# RGB-mic.net
KiCad netlist of a schematic drawn in Altium Designer
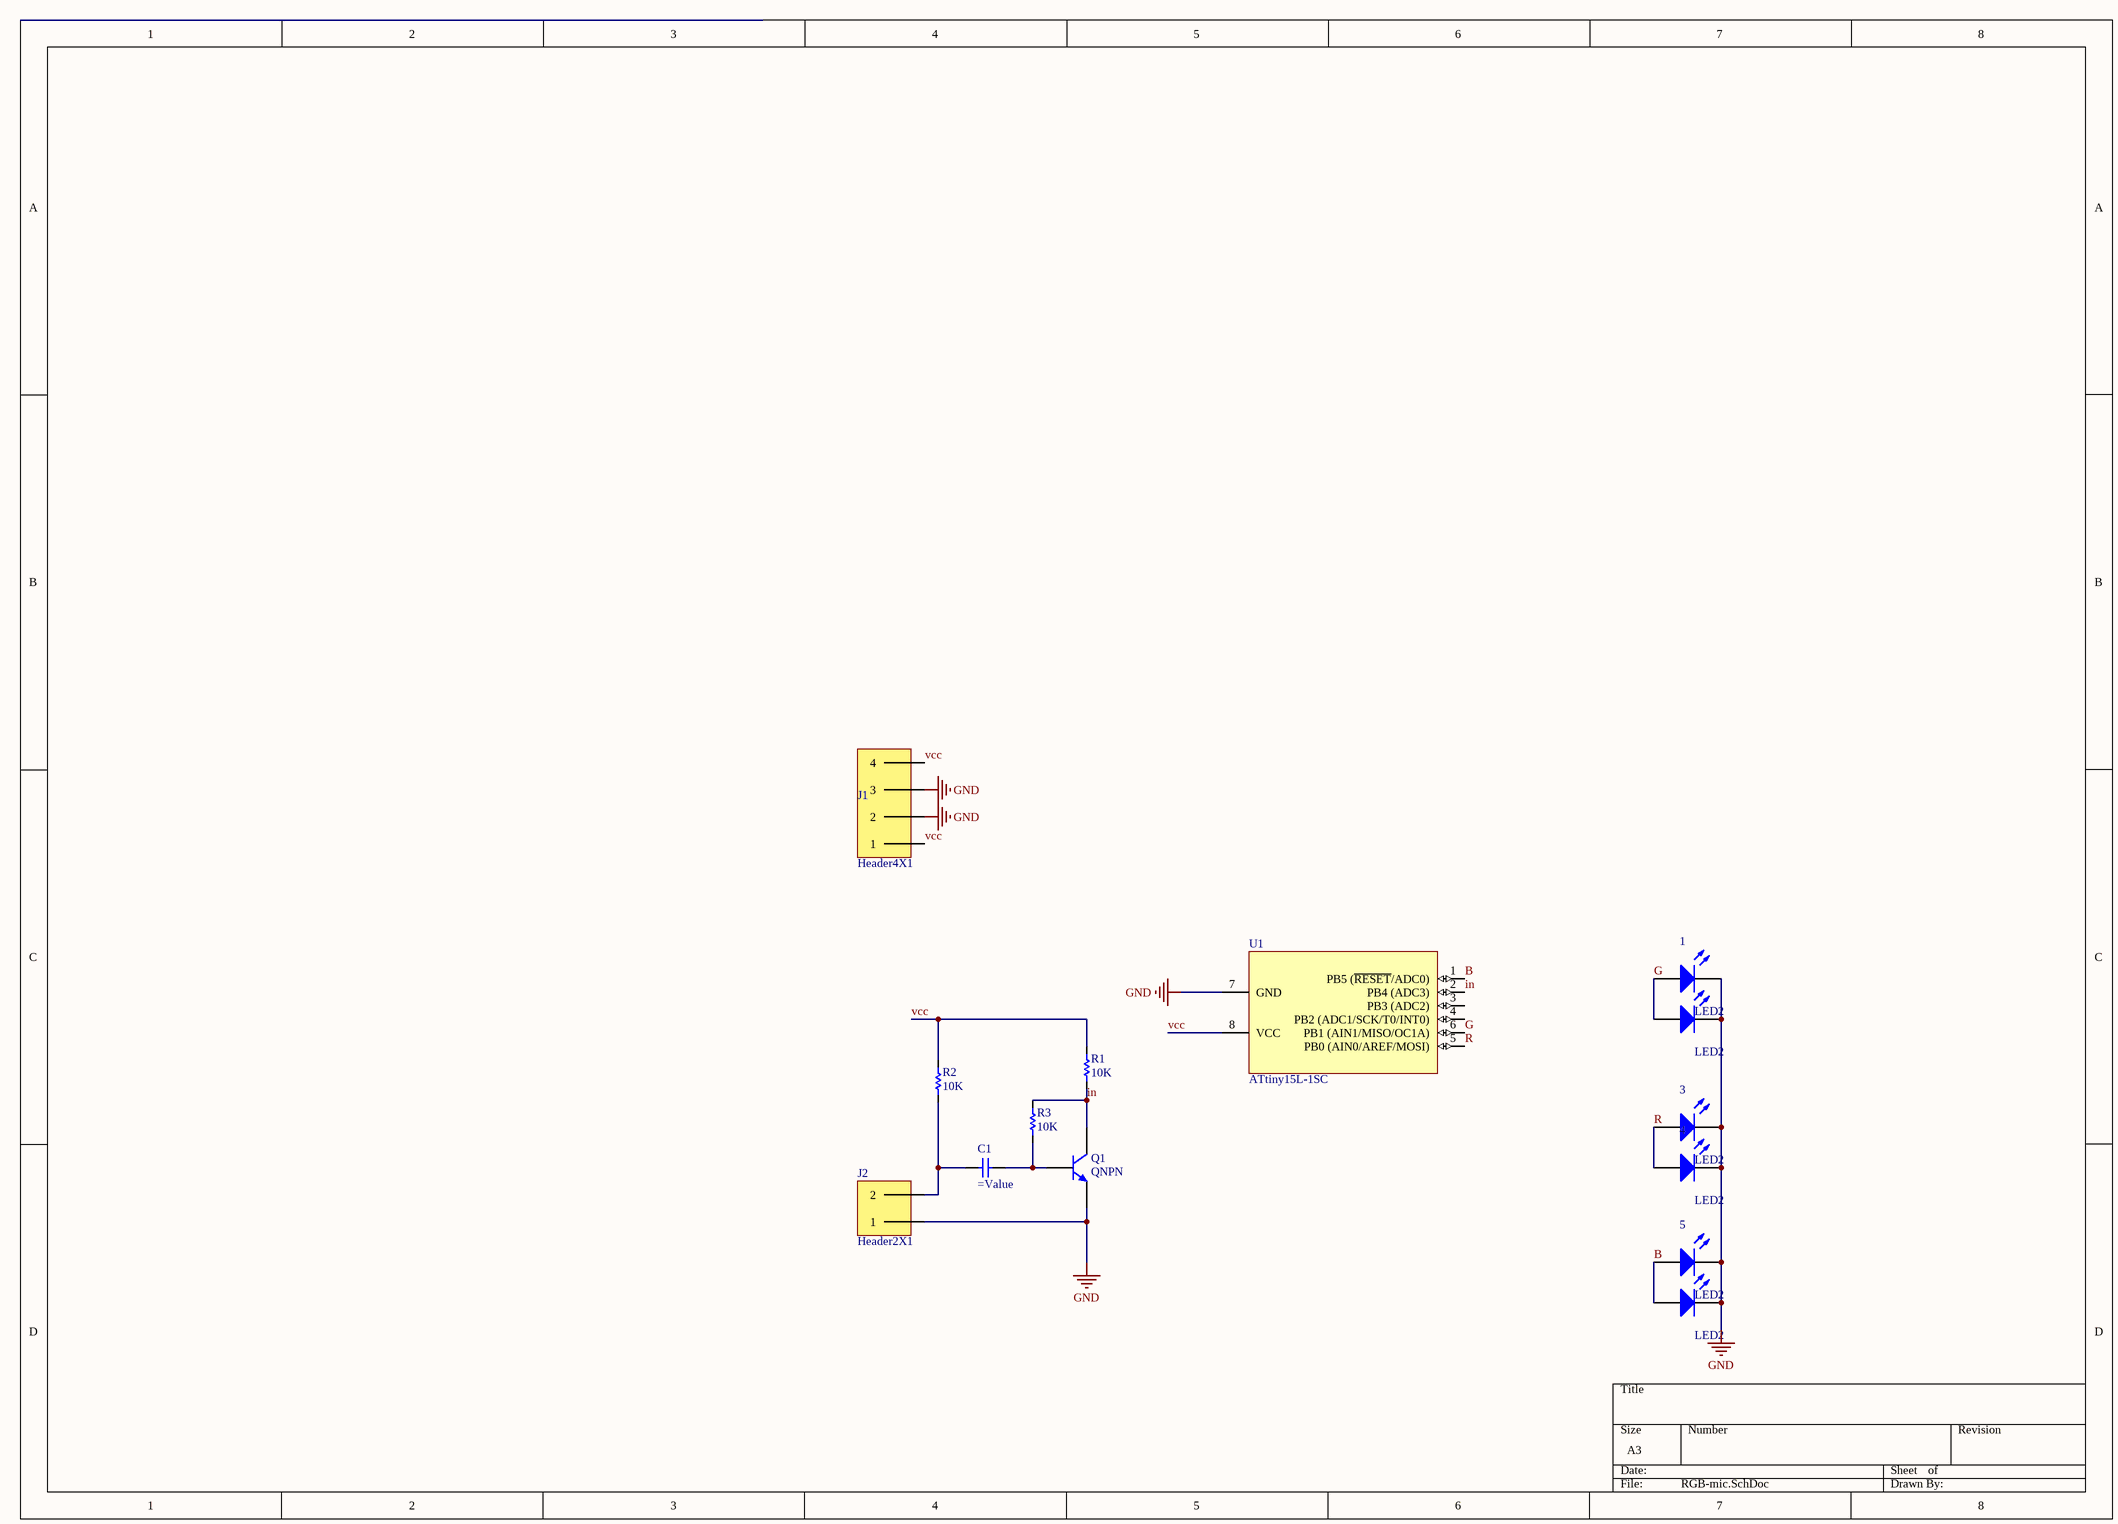
[diagram p0: RGB-mic.SchDoc]

(export (version "E")
  (design (tool "Eeschema 10.0.6"))
  (components
    (comp (ref "1")
      (value "LED2")
      (footprint "RES 0805 (2012X06L)")
      (description "Typical RED, GREEN, YELLOW, AMBER GaAs LED")
      (fields (field (name "PUBLISHER") "Altium Limited"))
      (libsource (lib "Miscellaneous Devices") (part "LED2"))
    )
    (comp (ref "2")
      (value "LED2")
      (footprint "RES 0805 (2012X06L)")
      (description "Typical RED, GREEN, YELLOW, AMBER GaAs LED")
      (fields (field (name "PUBLISHER") "Altium Limited"))
      (libsource (lib "Miscellaneous Devices") (part "LED2"))
    )
    (comp (ref "3")
      (value "LED2")
      (footprint "RES 0805 (2012X06L)")
      (description "Typical RED, GREEN, YELLOW, AMBER GaAs LED")
      (fields (field (name "PUBLISHER") "Altium Limited"))
      (libsource (lib "Miscellaneous Devices") (part "LED2"))
    )
    (comp (ref "4")
      (value "LED2")
      (footprint "RES 0805 (2012X06L)")
      (description "Typical RED, GREEN, YELLOW, AMBER GaAs LED")
      (fields (field (name "PUBLISHER") "Altium Limited"))
      (libsource (lib "Miscellaneous Devices") (part "LED2"))
    )
    (comp (ref "5")
      (value "LED2")
      (footprint "RES 0805 (2012X06L)")
      (description "Typical RED, GREEN, YELLOW, AMBER GaAs LED")
      (fields (field (name "PUBLISHER") "Altium Limited"))
      (libsource (lib "Miscellaneous Devices") (part "LED2"))
    )
    (comp (ref "6")
      (value "LED2")
      (footprint "RES 0805 (2012X06L)")
      (description "Typical RED, GREEN, YELLOW, AMBER GaAs LED")
      (fields (field (name "PUBLISHER") "Altium Limited"))
      (libsource (lib "Miscellaneous Devices") (part "LED2"))
    )
    (comp (ref "C1")
      (value "~")
      (footprint "CAP 1206")
      (description "Capacitor")
      (libsource (lib "AltiumLib1") (part "Capacitor"))
    )
    (comp (ref "J1")
      (value "Header4X1")
      (footprint "HEADER 4X1")
      (libsource (lib "AltiumLib1") (part "Header4X1"))
    )
    (comp (ref "J2")
      (value "Header2X1")
      (footprint "Header 2X1")
      (libsource (lib "AltiumLib1") (part "Header2X1"))
    )
    (comp (ref "Q1")
      (value "QNPN")
      (footprint "SOT-23B_L")
      (description "NPN Bipolar Transistor")
      (fields (field (name "PUBLISHER") "Altium Limited"))
      (libsource (lib "Miscellaneous Devices") (part "QNPN"))
    )
    (comp (ref "R1")
      (value "10K")
      (footprint "RES 1206 (3216X08L)")
      (description "Resistor")
      (fields (field (name "TOLERANCE") "5%") (field (name "POWER") "1/4 W"))
      (libsource (lib "AltiumLib1") (part "Resistor"))
    )
    (comp (ref "R2")
      (value "10K")
      (footprint "RES 1206 (3216X08L)")
      (description "Resistor")
      (fields (field (name "TOLERANCE") "5%") (field (name "POWER") "1/4 W"))
      (libsource (lib "AltiumLib1") (part "Resistor"))
    )
    (comp (ref "R3")
      (value "10K")
      (footprint "RES 1206 (3216X08L)")
      (description "Resistor")
      (fields (field (name "TOLERANCE") "5%") (field (name "POWER") "1/4 W"))
      (libsource (lib "AltiumLib1") (part "Resistor"))
    )
    (comp (ref "U1")
      (value "ATtiny15L-1SC")
      (footprint "8S2_N")
      (description "8-Bit AVR Microcontroller with 1K Byte of Flash Memory")
      (fields (field (name "PUBLISHER") "Altium Limited"))
      (libsource (lib "Atmel Microcontroller 8-Bit AVR") (part "ATtiny15L-1SC"))
    )
  )
  (nets
    (net (code "2") (name "/B") (class "Default")
      (node (ref "5") (pin "1") (pinfunction "A_1") (pintype "passive"))
      (node (ref "6") (pin "1") (pinfunction "A_1") (pintype "passive"))
      (node (ref "U1") (pin "1") (pinfunction "PB5_(~{RESET}/ADC0)_1") (pintype "bidirectional"))
    )
    (net (code "3") (name "/G") (class "Default")
      (node (ref "1") (pin "1") (pinfunction "A_1") (pintype "passive"))
      (node (ref "2") (pin "1") (pinfunction "A_1") (pintype "passive"))
      (node (ref "U1") (pin "6") (pinfunction "PB1_(AIN1/MISO/OC1A)_6") (pintype "bidirectional"))
    )
    (net (code "4") (name "/R") (class "Default")
      (node (ref "3") (pin "1") (pinfunction "A_1") (pintype "passive"))
      (node (ref "4") (pin "1") (pinfunction "A_1") (pintype "passive"))
      (node (ref "U1") (pin "5") (pinfunction "PB0_(AIN0/AREF/MOSI)_5") (pintype "bidirectional"))
    )
    (net (code "5") (name "/in") (class "Default")
      (node (ref "Q1") (pin "1") (pinfunction "C_1") (pintype "passive"))
      (node (ref "R1") (pin "1") (pinfunction "1_1") (pintype "passive"))
      (node (ref "R3") (pin "2") (pinfunction "2_2") (pintype "passive"))
      (node (ref "U1") (pin "2") (pinfunction "PB4_(ADC3)_2") (pintype "bidirectional"))
    )
    (net (code "6") (name "/vcc") (class "Default")
      (node (ref "J1") (pin "1") (pinfunction "1_1") (pintype "passive"))
      (node (ref "J1") (pin "4") (pinfunction "4_4") (pintype "passive"))
      (node (ref "R1") (pin "2") (pinfunction "2_2") (pintype "passive"))
      (node (ref "R2") (pin "2") (pinfunction "2_2") (pintype "passive"))
      (node (ref "U1") (pin "8") (pinfunction "VCC_8") (pintype "power_in"))
    )
    (net (code "7") (name "GND") (class "Default")
      (node (ref "1") (pin "2") (pinfunction "K_2") (pintype "passive"))
      (node (ref "2") (pin "2") (pinfunction "K_2") (pintype "passive"))
      (node (ref "3") (pin "2") (pinfunction "K_2") (pintype "passive"))
      (node (ref "4") (pin "2") (pinfunction "K_2") (pintype "passive"))
      (node (ref "5") (pin "2") (pinfunction "K_2") (pintype "passive"))
      (node (ref "6") (pin "2") (pinfunction "K_2") (pintype "passive"))
      (node (ref "J1") (pin "2") (pinfunction "2_2") (pintype "passive"))
      (node (ref "J1") (pin "3") (pinfunction "3_3") (pintype "passive"))
      (node (ref "J2") (pin "1") (pinfunction "1_1") (pintype "passive"))
      (node (ref "Q1") (pin "3") (pinfunction "E_3") (pintype "passive"))
      (node (ref "U1") (pin "7") (pinfunction "GND_7") (pintype "power_in"))
    )
    (net (code "8") (name "Net-(C1-+)") (class "Default")
      (node (ref "C1") (pin "1") (pinfunction "+_1") (pintype "passive"))
      (node (ref "J2") (pin "2") (pinfunction "2_2") (pintype "passive"))
      (node (ref "R2") (pin "1") (pinfunction "1_1") (pintype "passive"))
    )
    (net (code "9") (name "Net-(C1--)") (class "Default")
      (node (ref "C1") (pin "2") (pinfunction "-_2") (pintype "passive"))
      (node (ref "Q1") (pin "2") (pinfunction "B_2") (pintype "passive"))
      (node (ref "R3") (pin "1") (pinfunction "1_1") (pintype "passive"))
    )
    (net (code "10") (name "unconnected-(U1-PB2_(ADC1{slash}SCK{slash}T0{slash}INT0)-Pad4)") (class "Default")
      (node (ref "U1") (pin "4") (pinfunction "PB2_(ADC1/SCK/T0/INT0)_4") (pintype "bidirectional"))
    )
    (net (code "11") (name "unconnected-(U1-PB3_(ADC2)-Pad3)") (class "Default")
      (node (ref "U1") (pin "3") (pinfunction "PB3_(ADC2)_3") (pintype "bidirectional"))
    )
  )
)
